# Blinky.net
KiCad netlist of a schematic drawn in EAGLE
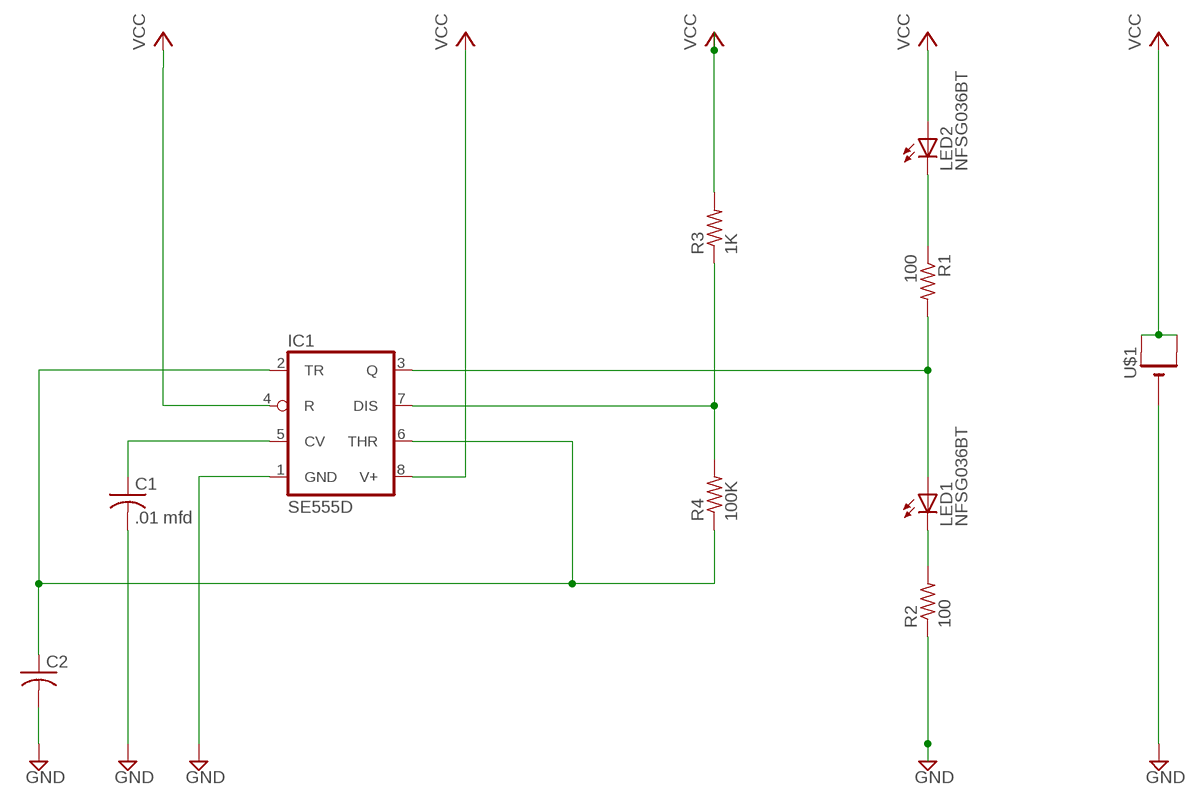
[diagram p0: schematic, sheet 1]

(export (version "E")
  (design (tool "Eeschema 10.0.6"))
  (components
    (comp (ref "C1")
      (value ".01 mfd")
      (footprint "eagle-import:C0805")
      (libsource (lib "eagle-import") (part "C-USC0805"))
    )
    (comp (ref "C2")
      (value "C-USC0805")
      (footprint "eagle-import:C0805")
      (libsource (lib "eagle-import") (part "C-USC0805"))
    )
    (comp (ref "IC1")
      (value "SE555D")
      (footprint "eagle-import:SO08")
      (libsource (lib "eagle-import") (part "555DSE"))
    )
    (comp (ref "LED1")
      (value "NFSG036BT")
      (footprint "eagle-import:NFSG036BT")
      (libsource (lib "eagle-import") (part "NFSG036BT"))
    )
    (comp (ref "LED2")
      (value "NFSG036BT")
      (footprint "eagle-import:NFSG036BT")
      (libsource (lib "eagle-import") (part "NFSG036BT"))
    )
    (comp (ref "R1")
      (value "100")
      (footprint "eagle-import:M0805")
      (libsource (lib "eagle-import") (part "R-US_M0805"))
    )
    (comp (ref "R2")
      (value "100")
      (footprint "eagle-import:M0805")
      (libsource (lib "eagle-import") (part "R-US_M0805"))
    )
    (comp (ref "R3")
      (value "1K")
      (footprint "eagle-import:M0805")
      (libsource (lib "eagle-import") (part "R-US_M0805"))
    )
    (comp (ref "R4")
      (value "100K")
      (footprint "eagle-import:M0805")
      (libsource (lib "eagle-import") (part "R-US_M0805"))
    )
    (comp (ref "U$1")
      (value "CR1220THM")
      (footprint "eagle-import:CR1220-THM")
      (libsource (lib "eagle-import") (part "CR1220THM"))
    )
  )
  (nets
    (net (code "1") (name "GND") (class "Default")
      (node (ref "C1") (pin "2") (pinfunction "2_2") (pintype "passive"))
      (node (ref "C2") (pin "2") (pinfunction "2_2") (pintype "passive"))
      (node (ref "IC1") (pin "1") (pinfunction "GND_1") (pintype "power_in"))
      (node (ref "R2") (pin "1") (pinfunction "1_1") (pintype "passive"))
      (node (ref "U$1") (pin "-") (pinfunction "-_-") (pintype "passive"))
    )
    (net (code "2") (name "Net-(IC1-CV)") (class "Default")
      (node (ref "C1") (pin "1") (pinfunction "1_1") (pintype "passive"))
      (node (ref "IC1") (pin "5") (pinfunction "CV_5") (pintype "input"))
    )
    (net (code "3") (name "Net-(IC1-DIS)") (class "Default")
      (node (ref "IC1") (pin "7") (pinfunction "DIS_7") (pintype "input"))
      (node (ref "R3") (pin "1") (pinfunction "1_1") (pintype "passive"))
      (node (ref "R4") (pin "2") (pinfunction "2_2") (pintype "passive"))
    )
    (net (code "4") (name "Net-(IC1-Q)") (class "Default")
      (node (ref "IC1") (pin "3") (pinfunction "Q_3") (pintype "output"))
      (node (ref "LED1") (pin "A") (pinfunction "A_A") (pintype "passive"))
      (node (ref "R1") (pin "2") (pinfunction "2_2") (pintype "passive"))
    )
    (net (code "5") (name "Net-(IC1-THR)") (class "Default")
      (node (ref "C2") (pin "1") (pinfunction "1_1") (pintype "passive"))
      (node (ref "IC1") (pin "2") (pinfunction "TR_2") (pintype "input"))
      (node (ref "IC1") (pin "6") (pinfunction "THR_6") (pintype "input"))
      (node (ref "R4") (pin "1") (pinfunction "1_1") (pintype "passive"))
    )
    (net (code "6") (name "Net-(LED1-PadC)") (class "Default")
      (node (ref "LED1") (pin "C") (pinfunction "C_C") (pintype "passive"))
      (node (ref "R2") (pin "2") (pinfunction "2_2") (pintype "passive"))
    )
    (net (code "7") (name "Net-(LED2-PadC)") (class "Default")
      (node (ref "LED2") (pin "C") (pinfunction "C_C") (pintype "passive"))
      (node (ref "R1") (pin "1") (pinfunction "1_1") (pintype "passive"))
    )
    (net (code "8") (name "VCC") (class "Default")
      (node (ref "IC1") (pin "4") (pinfunction "R_4") (pintype "input"))
      (node (ref "IC1") (pin "8") (pinfunction "V+_8") (pintype "power_in"))
      (node (ref "LED2") (pin "A") (pinfunction "A_A") (pintype "passive"))
      (node (ref "R3") (pin "2") (pinfunction "2_2") (pintype "passive"))
      (node (ref "U$1") (pin "+1") (pinfunction "+_+1") (pintype "passive"))
      (node (ref "U$1") (pin "+2") (pinfunction "+1_+2") (pintype "passive"))
    )
  )
)
